# ALIM_MOSFET.net
KiCad netlist of a schematic drawn in Altium Designer
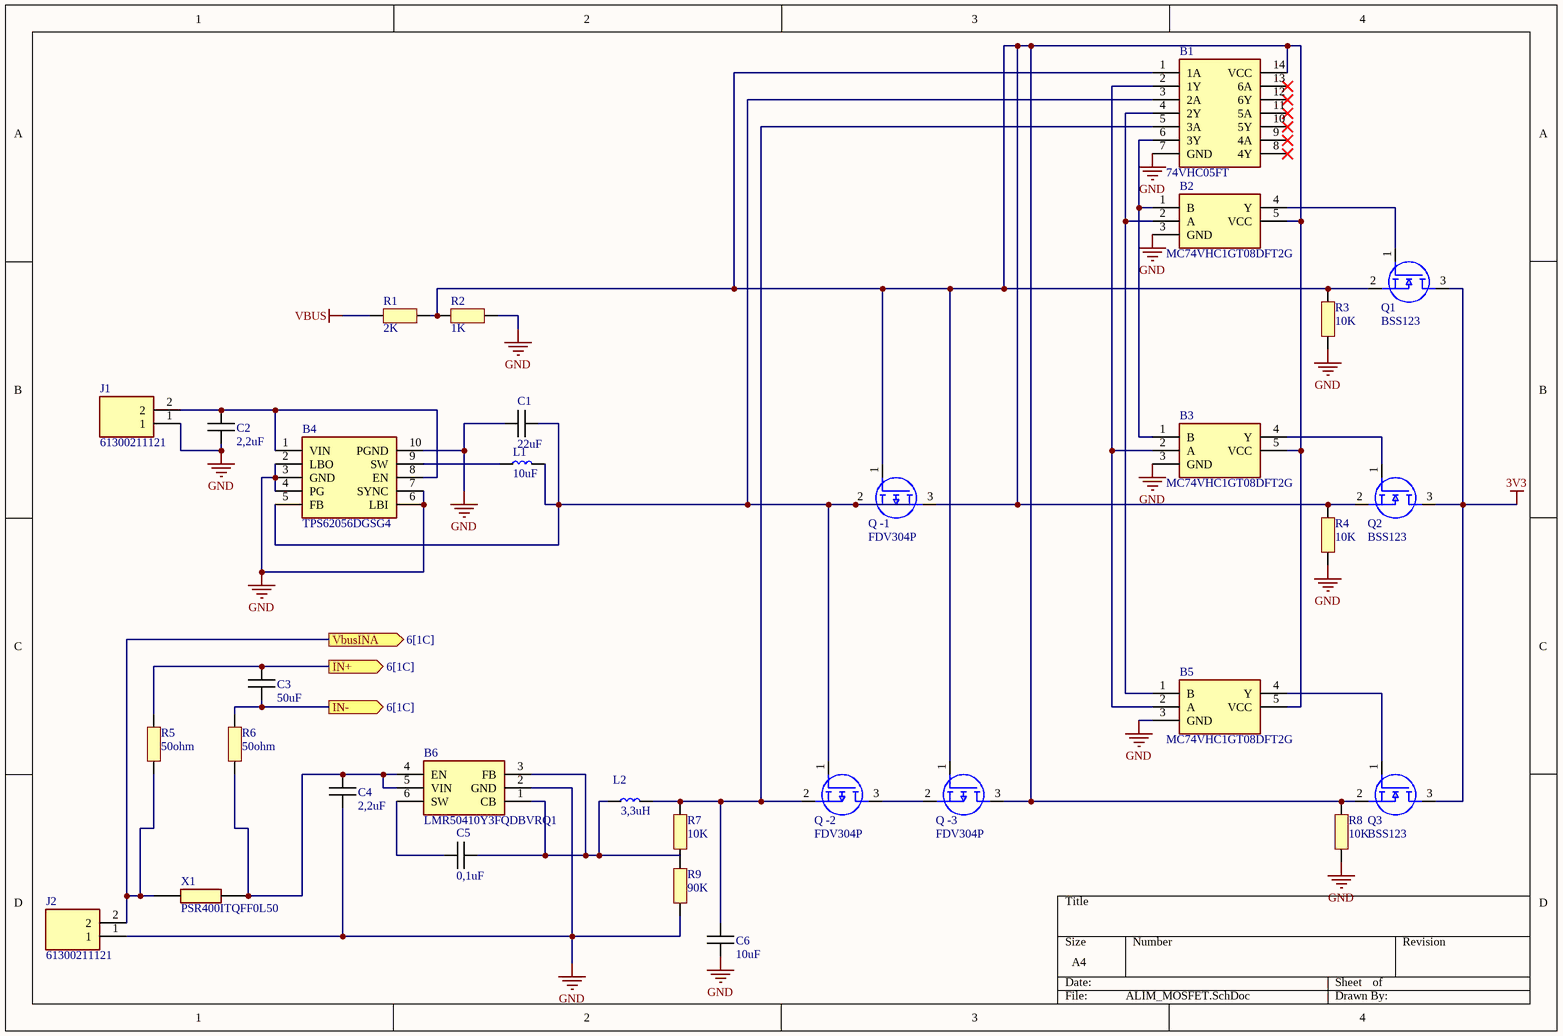
[diagram p0: ALIM_MOSFET.SchDoc]

(export (version "E")
  (design (tool "Eeschema 10.0.6"))
  (components
    (comp (ref "B1")
      (value "74VHC05FT")
      (footprint "SOP65P640X120-14N")
      (description "Logic Gates CMOS LOGIC IC INVERTER")
      (fields (field (name "MOUSER PART NUMBER") "757-74VHC05FT"))
      (libsource (lib "SCHLibrary") (part "74VHC05FT"))
    )
    (comp (ref "B2")
      (value "MC74VHC1GT08DFT2G")
      (footprint "SOT65P210X110-5N")
      (description "Single 2-Input AND Gate, TTL Level")
      (libsource (lib "SCHLibrary") (part "MC74VHC1GT08DFT2G"))
    )
    (comp (ref "B3")
      (value "MC74VHC1GT08DFT2G")
      (footprint "SOT65P210X110-5N")
      (description "Single 2-Input AND Gate, TTL Level")
      (libsource (lib "SCHLibrary") (part "MC74VHC1GT08DFT2G"))
    )
    (comp (ref "B4")
      (value "TPS62056DGSG4")
      (footprint "SOP50P490X110-10N")
      (fields (field (name "MOUSER PART NUMBER") "595-TPS62056DGSG4"))
      (libsource (lib "SCHLibrary") (part "TPS62056DGSG4"))
    )
    (comp (ref "B5")
      (value "MC74VHC1GT08DFT2G")
      (footprint "SOT65P210X110-5N")
      (description "Single 2-Input AND Gate, TTL Level")
      (libsource (lib "SCHLibrary") (part "MC74VHC1GT08DFT2G"))
    )
    (comp (ref "B6")
      (value "LMR50410Y3FQDBVRQ1")
      (footprint "SOT95P280X145-6N")
      (fields (field (name "MOUSER PART NUMBER") "595-R50410Y3FQDBVRQ1"))
      (libsource (lib "SCHLibrary") (part "LMR50410Y3FQDBVRQ1"))
    )
    (comp (ref "C1")
      (value "22uF")
      (footprint "CAPC1005X06N")
      (libsource (lib "SCHLibrary") (part "Capacitor"))
    )
    (comp (ref "C2")
      (value "2,2uF")
      (footprint "CAPC1005X06N")
      (libsource (lib "SCHLibrary") (part "Capacitor"))
    )
    (comp (ref "C3")
      (value "50uF")
      (footprint "CAPC1005X06N")
      (libsource (lib "SCHLibrary") (part "Capacitor"))
    )
    (comp (ref "C4")
      (value "2,2uF")
      (footprint "CAPC1005X06N")
      (libsource (lib "SCHLibrary") (part "Capacitor"))
    )
    (comp (ref "C5")
      (value "0,1uF")
      (footprint "CAPC1005X06N")
      (libsource (lib "SCHLibrary") (part "Capacitor"))
    )
    (comp (ref "C6")
      (value "10uF")
      (footprint "CAPC1005X06N")
      (libsource (lib "SCHLibrary") (part "Capacitor"))
    )
    (comp (ref "J1")
      (value "61300211121")
      (footprint "61300211121")
      (description "WURTH ELEKTRONIK - 61300211121 - HEADER, 2.54MM, PIN, THT, VERTICAL, 2WAY")
      (libsource (lib "SCHLibrary") (part "61300211121"))
    )
    (comp (ref "J2")
      (value "61300211121")
      (footprint "61300211121")
      (description "WURTH ELEKTRONIK - 61300211121 - HEADER, 2.54MM, PIN, THT, VERTICAL, 2WAY")
      (libsource (lib "SCHLibrary") (part "61300211121"))
    )
    (comp (ref "L1") (value "10uF") (footprint "LQPC1005X06N") (libsource (lib "SCHLibrary") (part "Bobine")))
    (comp (ref "L2")
      (value "3,3uH")
      (footprint "LQPC1005X06N")
      (libsource (lib "SCHLibrary") (part "Bobine"))
    )
    (comp (ref "Q -1")
      (value "FDV304P")
      (footprint "SOT95P251X112-3N")
      (fields (field (name "MOUSER PART NUMBER") "512-FDV304P"))
      (libsource (lib "SCHLibrary") (part "FDV304P"))
    )
    (comp (ref "Q -2")
      (value "FDV304P")
      (footprint "SOT95P251X112-3N")
      (fields (field (name "MOUSER PART NUMBER") "512-FDV304P"))
      (libsource (lib "SCHLibrary") (part "FDV304P"))
    )
    (comp (ref "Q -3")
      (value "FDV304P")
      (footprint "SOT95P251X112-3N")
      (fields (field (name "MOUSER PART NUMBER") "512-FDV304P"))
      (libsource (lib "SCHLibrary") (part "FDV304P"))
    )
    (comp (ref "Q1")
      (value "BSS123")
      (footprint "BSS123")
      (description "BSS123 N-Channel MOSFET, 170 mA, 100 V PowerTrench, 3-Pin SOT-23 ON Semiconductor")
      (libsource (lib "SCHLibrary") (part "BSS123"))
    )
    (comp (ref "Q2")
      (value "BSS123")
      (footprint "BSS123")
      (description "BSS123 N-Channel MOSFET, 170 mA, 100 V PowerTrench, 3-Pin SOT-23 ON Semiconductor")
      (libsource (lib "SCHLibrary") (part "BSS123"))
    )
    (comp (ref "Q3")
      (value "BSS123")
      (footprint "BSS123")
      (description "BSS123 N-Channel MOSFET, 170 mA, 100 V PowerTrench, 3-Pin SOT-23 ON Semiconductor")
      (libsource (lib "SCHLibrary") (part "BSS123"))
    )
    (comp (ref "R1") (value "2K") (footprint "RESC1005X06N") (libsource (lib "") (part "Resistor_2")))
    (comp (ref "R2") (value "1K") (footprint "RESC1005X06N") (libsource (lib "") (part "Resistor_2")))
    (comp (ref "R3")
      (value "10K")
      (footprint "RESC1005X06N")
      (libsource (lib "SCHLibrary") (part "Resistor"))
    )
    (comp (ref "R4")
      (value "10K")
      (footprint "RESC1005X06N")
      (libsource (lib "SCHLibrary") (part "Resistor"))
    )
    (comp (ref "R5") (value "50ohm") (footprint "RESC1005X06N") (libsource (lib "") (part "Resistor_1")))
    (comp (ref "R6") (value "50ohm") (footprint "RESC1005X06N") (libsource (lib "") (part "Resistor_1")))
    (comp (ref "R7")
      (value "10K")
      (footprint "RESC1005X06N")
      (libsource (lib "SCHLibrary") (part "Resistor"))
    )
    (comp (ref "R8")
      (value "10K")
      (footprint "RESC1005X06N")
      (libsource (lib "SCHLibrary") (part "Resistor"))
    )
    (comp (ref "R9")
      (value "90K")
      (footprint "RESC1005X06N")
      (libsource (lib "SCHLibrary") (part "Resistor"))
    )
    (comp (ref "X1")
      (value "PSR400ITQFF0L50")
      (footprint "RESC10052X200N")
      (fields (field (name "MOUSER PART NUMBER") "755-PSR400ITQFF0L50"))
      (libsource (lib "SCHLibrary") (part "PSR400ITQFF0L50"))
    )
  )
  (nets
    (net (code "1") (name "/IN+") (class "Default")
      (node (ref "C3") (pin "1") (pinfunction "1_1") (pintype "passive"))
      (node (ref "R5") (pin "2") (pinfunction "2_2") (pintype "passive"))
    )
    (net (code "2") (name "/IN-") (class "Default")
      (node (ref "C3") (pin "2") (pinfunction "2_2") (pintype "passive"))
      (node (ref "R6") (pin "2") (pinfunction "2_2") (pintype "passive"))
    )
    (net (code "3") (name "/VbusINA") (class "Default")
      (node (ref "J2") (pin "2") (pinfunction "2_2") (pintype "passive"))
      (node (ref "R5") (pin "1") (pinfunction "1_1") (pintype "passive"))
      (node (ref "X1") (pin "1") (pinfunction "1_1") (pintype "passive"))
    )
    (net (code "4") (name "3V3") (class "Default")
      (node (ref "Q1") (pin "3") (pinfunction "D_3") (pintype "passive"))
      (node (ref "Q2") (pin "3") (pinfunction "D_3") (pintype "passive"))
      (node (ref "Q3") (pin "3") (pinfunction "D_3") (pintype "passive"))
    )
    (net (code "5") (name "GND") (class "Default")
      (node (ref "B1") (pin "7") (pinfunction "GND_7") (pintype "passive"))
      (node (ref "B2") (pin "3") (pinfunction "GND_3") (pintype "passive"))
      (node (ref "B3") (pin "3") (pinfunction "GND_3") (pintype "passive"))
      (node (ref "B4") (pin "10") (pinfunction "PGND_10") (pintype "passive"))
      (node (ref "B4") (pin "2") (pinfunction "LBO_2") (pintype "passive"))
      (node (ref "B4") (pin "3") (pinfunction "GND_3") (pintype "passive"))
      (node (ref "B4") (pin "4") (pinfunction "PG_4") (pintype "passive"))
      (node (ref "B4") (pin "6") (pinfunction "LBI_6") (pintype "passive"))
      (node (ref "B4") (pin "7") (pinfunction "SYNC_7") (pintype "passive"))
      (node (ref "B5") (pin "3") (pinfunction "GND_3") (pintype "passive"))
      (node (ref "B6") (pin "2") (pinfunction "GND_2") (pintype "passive"))
      (node (ref "C1") (pin "2") (pinfunction "2_2") (pintype "passive"))
      (node (ref "C2") (pin "2") (pinfunction "2_2") (pintype "passive"))
      (node (ref "C4") (pin "2") (pinfunction "2_2") (pintype "passive"))
      (node (ref "C6") (pin "2") (pinfunction "2_2") (pintype "passive"))
      (node (ref "J1") (pin "1") (pinfunction "1_1") (pintype "passive"))
      (node (ref "J2") (pin "1") (pinfunction "1_1") (pintype "passive"))
      (node (ref "R2") (pin "2") (pinfunction "2_2") (pintype "passive"))
      (node (ref "R3") (pin "2") (pinfunction "2_2") (pintype "passive"))
      (node (ref "R4") (pin "2") (pinfunction "2_2") (pintype "passive"))
      (node (ref "R8") (pin "2") (pinfunction "2_2") (pintype "passive"))
      (node (ref "R9") (pin "2") (pinfunction "2_2") (pintype "passive"))
    )
    (net (code "6") (name "Net-(B1-1A)") (class "Default")
      (node (ref "B1") (pin "1") (pinfunction "1A_1") (pintype "passive"))
      (node (ref "B1") (pin "14") (pinfunction "VCC_14") (pintype "passive"))
      (node (ref "B2") (pin "5") (pinfunction "VCC_5") (pintype "passive"))
      (node (ref "B3") (pin "5") (pinfunction "VCC_5") (pintype "passive"))
      (node (ref "B5") (pin "5") (pinfunction "VCC_5") (pintype "passive"))
      (node (ref "Q -1") (pin "1") (pinfunction "G_1") (pintype "passive"))
      (node (ref "Q -1") (pin "3") (pinfunction "D_3") (pintype "passive"))
      (node (ref "Q -3") (pin "1") (pinfunction "G_1") (pintype "passive"))
      (node (ref "Q -3") (pin "3") (pinfunction "D_3") (pintype "passive"))
      (node (ref "Q1") (pin "2") (pinfunction "S_2") (pintype "passive"))
      (node (ref "Q2") (pin "2") (pinfunction "S_2") (pintype "passive"))
      (node (ref "Q3") (pin "2") (pinfunction "S_2") (pintype "passive"))
      (node (ref "R1") (pin "2") (pinfunction "2_2") (pintype "passive"))
      (node (ref "R2") (pin "1") (pinfunction "1_1") (pintype "passive"))
      (node (ref "R3") (pin "1") (pinfunction "1_1") (pintype "passive"))
      (node (ref "R4") (pin "1") (pinfunction "1_1") (pintype "passive"))
      (node (ref "R8") (pin "1") (pinfunction "1_1") (pintype "passive"))
    )
    (net (code "7") (name "Net-(B1-1Y)") (class "Default")
      (node (ref "B1") (pin "2") (pinfunction "1Y_2") (pintype "passive"))
      (node (ref "B3") (pin "2") (pinfunction "A_2") (pintype "passive"))
      (node (ref "B5") (pin "2") (pinfunction "A_2") (pintype "passive"))
    )
    (net (code "8") (name "Net-(B1-2A)") (class "Default")
      (node (ref "B1") (pin "3") (pinfunction "2A_3") (pintype "passive"))
      (node (ref "B4") (pin "5") (pinfunction "FB_5") (pintype "passive"))
      (node (ref "C1") (pin "1") (pinfunction "1_1") (pintype "passive"))
      (node (ref "L1") (pin "2") (pinfunction "2_2") (pintype "passive"))
      (node (ref "Q -1") (pin "2") (pinfunction "S_2") (pintype "passive"))
      (node (ref "Q -2") (pin "1") (pinfunction "G_1") (pintype "passive"))
    )
    (net (code "9") (name "Net-(B1-2Y)") (class "Default")
      (node (ref "B1") (pin "4") (pinfunction "2Y_4") (pintype "passive"))
      (node (ref "B2") (pin "2") (pinfunction "A_2") (pintype "passive"))
      (node (ref "B5") (pin "1") (pinfunction "B_1") (pintype "passive"))
    )
    (net (code "10") (name "Net-(B1-3A)") (class "Default")
      (node (ref "B1") (pin "5") (pinfunction "3A_5") (pintype "passive"))
      (node (ref "C6") (pin "1") (pinfunction "1_1") (pintype "passive"))
      (node (ref "L2") (pin "2") (pinfunction "2_2") (pintype "passive"))
      (node (ref "Q -2") (pin "2") (pinfunction "S_2") (pintype "passive"))
      (node (ref "R7") (pin "1") (pinfunction "1_1") (pintype "passive"))
    )
    (net (code "11") (name "Net-(B1-3Y)") (class "Default")
      (node (ref "B1") (pin "6") (pinfunction "3Y_6") (pintype "passive"))
      (node (ref "B2") (pin "1") (pinfunction "B_1") (pintype "passive"))
      (node (ref "B3") (pin "1") (pinfunction "B_1") (pintype "passive"))
    )
    (net (code "12") (name "Net-(B2-Y)") (class "Default")
      (node (ref "B2") (pin "4") (pinfunction "Y_4") (pintype "passive"))
      (node (ref "Q1") (pin "1") (pinfunction "G_1") (pintype "passive"))
    )
    (net (code "13") (name "Net-(B3-Y)") (class "Default")
      (node (ref "B3") (pin "4") (pinfunction "Y_4") (pintype "passive"))
      (node (ref "Q2") (pin "1") (pinfunction "G_1") (pintype "passive"))
    )
    (net (code "14") (name "Net-(B4-EN)") (class "Default")
      (node (ref "B4") (pin "1") (pinfunction "VIN_1") (pintype "passive"))
      (node (ref "B4") (pin "8") (pinfunction "EN_8") (pintype "passive"))
      (node (ref "C2") (pin "1") (pinfunction "1_1") (pintype "passive"))
      (node (ref "J1") (pin "2") (pinfunction "2_2") (pintype "passive"))
    )
    (net (code "15") (name "Net-(B4-SW)") (class "Default")
      (node (ref "B4") (pin "9") (pinfunction "SW_9") (pintype "passive"))
      (node (ref "L1") (pin "1") (pinfunction "1_1") (pintype "passive"))
    )
    (net (code "16") (name "Net-(B5-Y)") (class "Default")
      (node (ref "B5") (pin "4") (pinfunction "Y_4") (pintype "passive"))
      (node (ref "Q3") (pin "1") (pinfunction "G_1") (pintype "passive"))
    )
    (net (code "17") (name "Net-(B6-CB)") (class "Default")
      (node (ref "B6") (pin "1") (pinfunction "CB_1") (pintype "passive"))
      (node (ref "B6") (pin "3") (pinfunction "FB_3") (pintype "passive"))
      (node (ref "C5") (pin "1") (pinfunction "1_1") (pintype "passive"))
      (node (ref "L2") (pin "1") (pinfunction "1_1") (pintype "passive"))
      (node (ref "R9") (pin "1") (pinfunction "1_1") (pintype "passive"))
    )
    (net (code "18") (name "Net-(B6-EN)") (class "Default")
      (node (ref "B6") (pin "4") (pinfunction "EN_4") (pintype "passive"))
      (node (ref "B6") (pin "5") (pinfunction "VIN_5") (pintype "passive"))
      (node (ref "C4") (pin "1") (pinfunction "1_1") (pintype "passive"))
      (node (ref "R6") (pin "1") (pinfunction "1_1") (pintype "passive"))
      (node (ref "X1") (pin "2") (pinfunction "2_2") (pintype "passive"))
    )
    (net (code "19") (name "Net-(B6-SW)") (class "Default")
      (node (ref "B6") (pin "6") (pinfunction "SW_6") (pintype "passive"))
      (node (ref "C5") (pin "2") (pinfunction "2_2") (pintype "passive"))
    )
    (net (code "20") (name "Net-(Q -2-D)") (class "Default")
      (node (ref "Q -2") (pin "3") (pinfunction "D_3") (pintype "passive"))
      (node (ref "Q -3") (pin "2") (pinfunction "S_2") (pintype "passive"))
    )
    (net (code "21") (name "VBUS") (class "Default")
      (node (ref "R1") (pin "1") (pinfunction "1_1") (pintype "passive"))
    )
    (net (code "22") (name "unconnected-(B1-4A-Pad9)") (class "Default")
      (node (ref "B1") (pin "9") (pinfunction "4A_9") (pintype "passive+no_connect"))
    )
    (net (code "23") (name "unconnected-(B1-4Y-Pad8)") (class "Default")
      (node (ref "B1") (pin "8") (pinfunction "4Y_8") (pintype "passive+no_connect"))
    )
    (net (code "24") (name "unconnected-(B1-5A-Pad11)") (class "Default")
      (node (ref "B1") (pin "11") (pinfunction "5A_11") (pintype "passive+no_connect"))
    )
    (net (code "25") (name "unconnected-(B1-5Y-Pad10)") (class "Default")
      (node (ref "B1") (pin "10") (pinfunction "5Y_10") (pintype "passive+no_connect"))
    )
    (net (code "26") (name "unconnected-(B1-6A-Pad13)") (class "Default")
      (node (ref "B1") (pin "13") (pinfunction "6A_13") (pintype "passive+no_connect"))
    )
    (net (code "27") (name "unconnected-(B1-6Y-Pad12)") (class "Default")
      (node (ref "B1") (pin "12") (pinfunction "6Y_12") (pintype "passive+no_connect"))
    )
    (net (code "28") (name "unconnected-(R7-Pad2)") (class "Default")
      (node (ref "R7") (pin "2") (pinfunction "2_2") (pintype "passive"))
    )
  )
)
